# Fdbk_1.net
KiCad netlist of a schematic drawn in Altium Designer
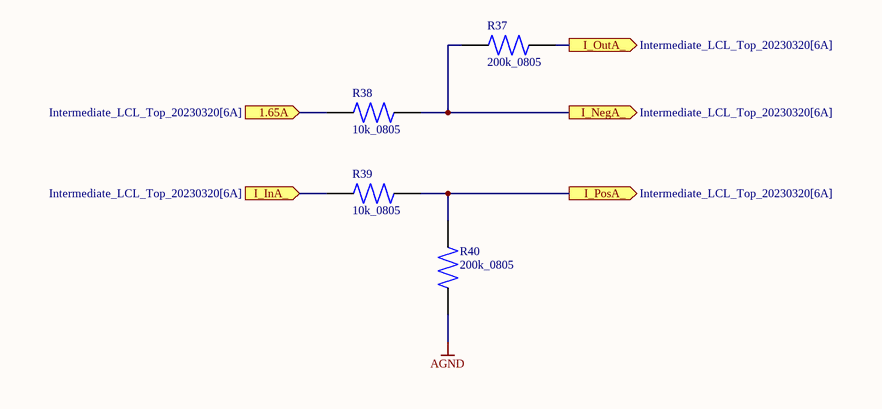
[diagram p0: Fdbk_1.SchDoc]

(export (version "E")
  (design (tool "Eeschema 10.0.6"))
  (components
    (comp (ref "R37")
      (value "200k_0805")
      (footprint "FYP_Components:0805 Resistor")
      (description "SMD Chip Resistor, 200 kohm, ± 1%, 125 mW, 0805 [2012 Metric], Thick Film, General Purpose")
      (fields (field (name "MF") "Bourns") (field (name "MP") "CRE2512-FZ-R007E-3"))
      (libsource (lib "FYP_Components") (part "CRCW0805200KFKEA"))
    )
    (comp (ref "R38")
      (value "10k_0805")
      (footprint "FYP_Components:0805 Resistor")
      (description "SMD Chip Resistor, 10 kohm, ± 1%, 125 mW, 0805 [2012 Metric], Thick Film, General Purpose")
      (fields (field (name "MF") "Bourns") (field (name "MP") "CRE2512-FZ-R007E-3"))
      (libsource (lib "FYP_Components") (part "CRCW080510K0FKEA"))
    )
    (comp (ref "R39")
      (value "10k_0805")
      (footprint "FYP_Components:0805 Resistor")
      (description "SMD Chip Resistor, 10 kohm, ± 1%, 125 mW, 0805 [2012 Metric], Thick Film, General Purpose")
      (fields (field (name "MF") "Bourns") (field (name "MP") "CRE2512-FZ-R007E-3"))
      (libsource (lib "FYP_Components") (part "CRCW080510K0FKEA"))
    )
    (comp (ref "R40")
      (value "200k_0805")
      (footprint "FYP_Components:0805 Resistor")
      (description "SMD Chip Resistor, 200 kohm, ± 1%, 125 mW, 0805 [2012 Metric], Thick Film, General Purpose")
      (fields (field (name "MF") "Bourns") (field (name "MP") "CRE2512-FZ-R007E-3"))
      (libsource (lib "FYP_Components") (part "CRCW0805200KFKEA"))
    )
  )
  (nets
    (net (code "1") (name "/1.65A") (class "Default")
      (node (ref "R38") (pin "1") (pinfunction "1_1") (pintype "passive"))
    )
    (net (code "2") (name "/I_InA_") (class "Default")
      (node (ref "R39") (pin "1") (pinfunction "1_1") (pintype "passive"))
    )
    (net (code "3") (name "/I_NegA_") (class "Default")
      (node (ref "R37") (pin "1") (pinfunction "1_1") (pintype "passive"))
      (node (ref "R38") (pin "2") (pinfunction "2_2") (pintype "passive"))
    )
    (net (code "4") (name "/I_OutA_") (class "Default")
      (node (ref "R37") (pin "2") (pinfunction "2_2") (pintype "passive"))
    )
    (net (code "5") (name "/I_PosA_") (class "Default")
      (node (ref "R39") (pin "2") (pinfunction "2_2") (pintype "passive"))
      (node (ref "R40") (pin "2") (pinfunction "2_2") (pintype "passive"))
    )
    (net (code "6") (name "AGND") (class "Default")
      (node (ref "R40") (pin "1") (pinfunction "1_1") (pintype "passive"))
    )
  )
)
